# Escorna_CPU_2_40Amt.net
KiCad netlist of a schematic drawn in EAGLE
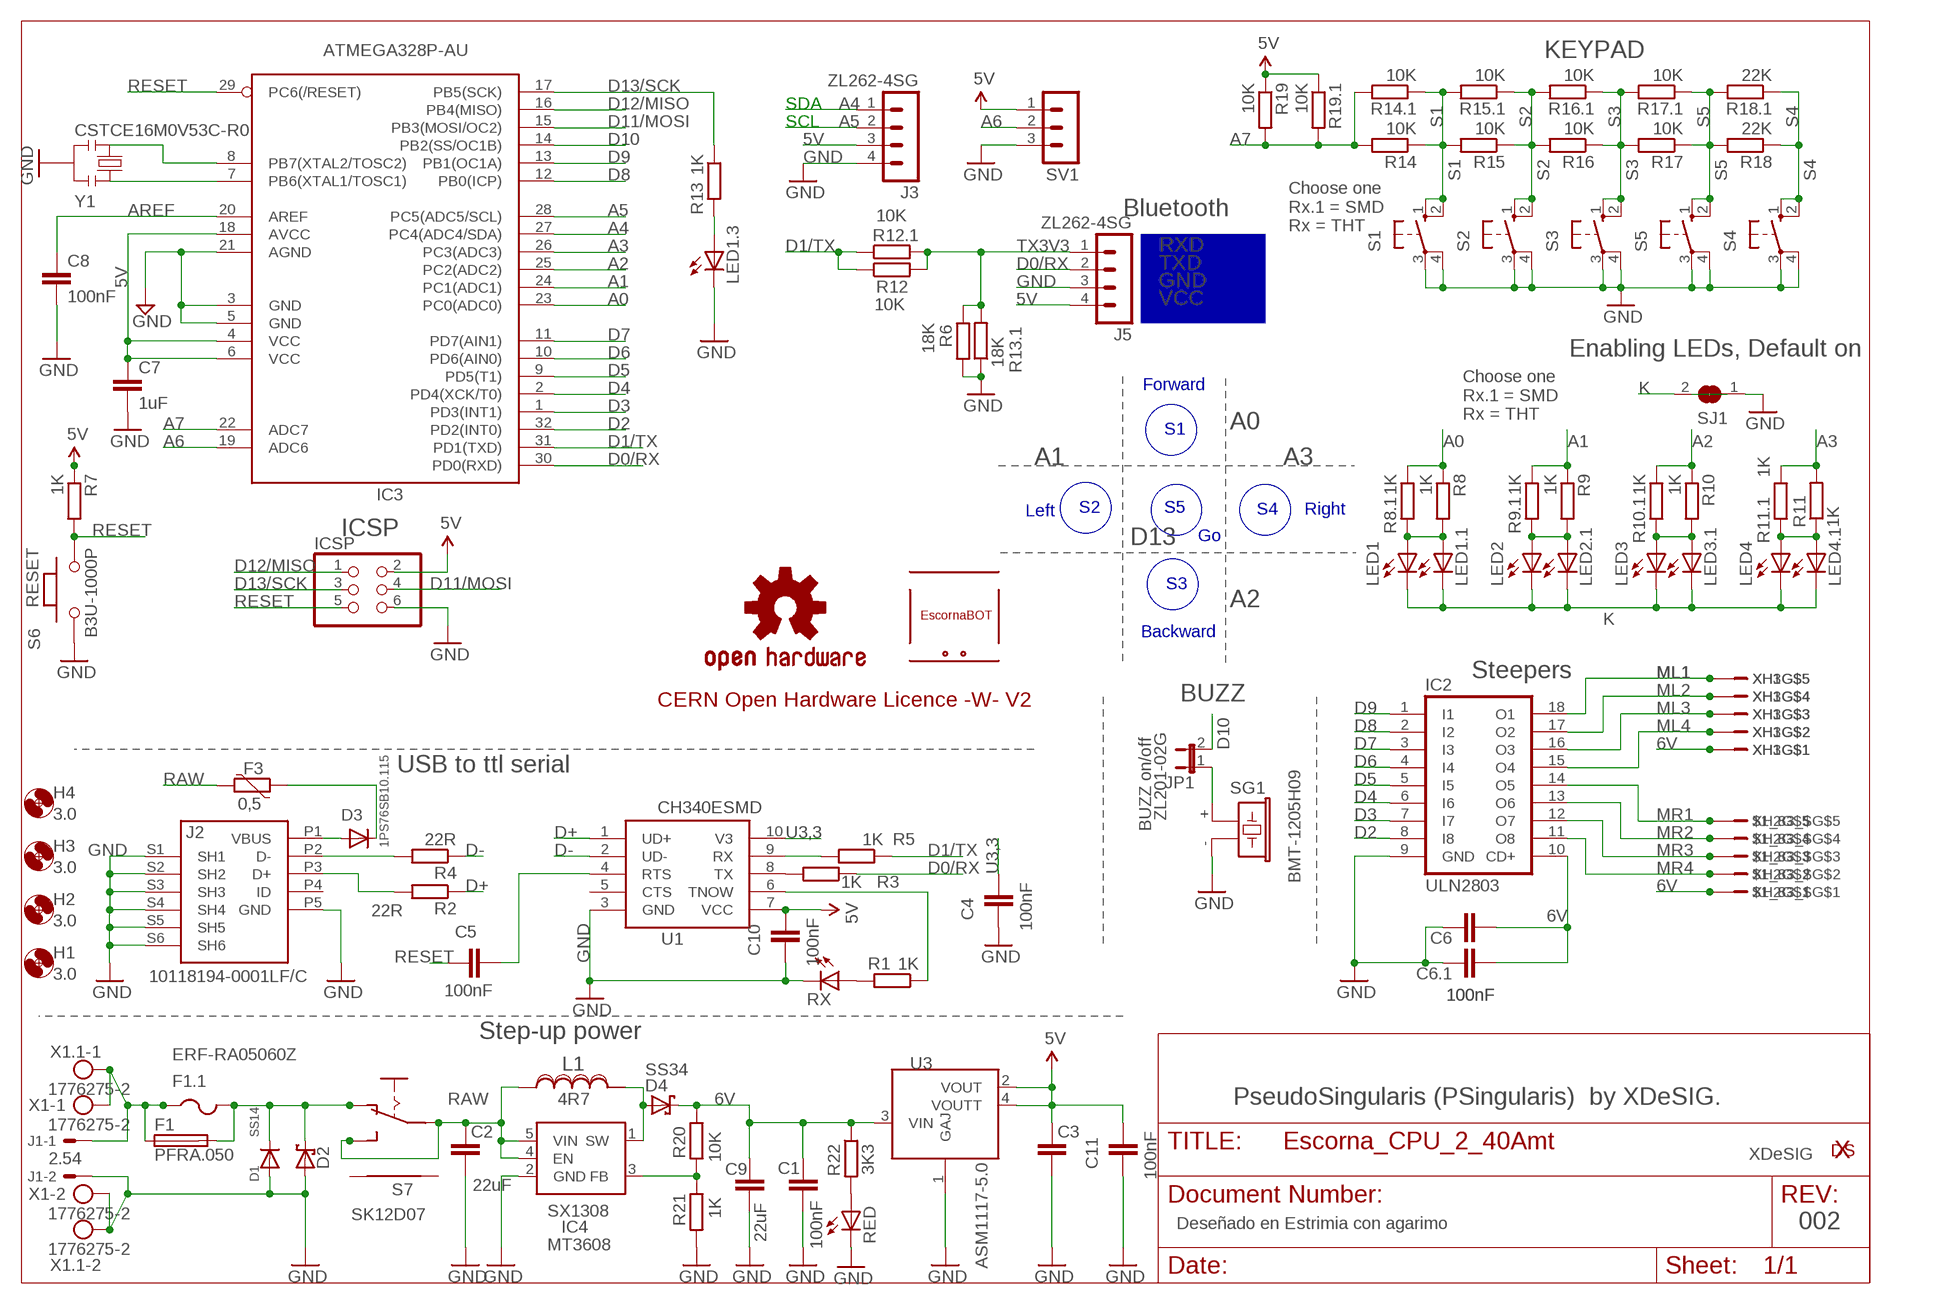
[diagram p0: schematic, sheet 1]

(export (version "E")
  (design (tool "Eeschema 10.0.6"))
  (components
    (comp (ref "$1_82_$")
      (value "XDESIG_XDESIG21")
      (footprint "eagle-import:XDESIG_XDESIG")
      (libsource (lib "eagle-import") (part "XDESIG_XDESIG21"))
    )
    (comp (ref "$1_83_$")
      (value "B5B-XH-A")
      (footprint "eagle-import:B5B-XH-A")
      (libsource (lib "eagle-import") (part "B5B-XH-A"))
    )
    (comp (ref "C1")
      (value "100nF")
      (footprint "eagle-import:C0603-ROUND")
      (fields (field (name "PART_NUMBER") "cl10b104kbnc"))
      (libsource (lib "eagle-import") (part "0015_100NF_0603"))
    )
    (comp (ref "C2")
      (value "22uF")
      (footprint "eagle-import:C1206K")
      (libsource (lib "eagle-import") (part "C-EUC1206K"))
    )
    (comp (ref "C3")
      (value "10uF")
      (footprint "eagle-import:C1206K")
      (libsource (lib "eagle-import") (part "C-EUC1206K"))
    )
    (comp (ref "C4")
      (value "100nF")
      (footprint "eagle-import:C0603-ROUND")
      (fields (field (name "PART_NUMBER") "cl10b104kbnc"))
      (libsource (lib "eagle-import") (part "0015_100NF_0603"))
    )
    (comp (ref "C5")
      (value "100nF")
      (footprint "eagle-import:C0603-ROUND")
      (fields (field (name "PART_NUMBER") "cl10b104kbnc"))
      (libsource (lib "eagle-import") (part "0015_100NF_0603"))
    )
    (comp (ref "C6")
      (value "100nF")
      (footprint "eagle-import:C025-024X044")
      (libsource (lib "eagle-import") (part "C-EU025-024X044"))
    )
    (comp (ref "C6.1")
      (value "100nF")
      (footprint "eagle-import:C0603K")
      (libsource (lib "eagle-import") (part "C-EUC0603K"))
    )
    (comp (ref "C7")
      (value "1uF")
      (footprint "eagle-import:C0603-ROUND")
      (fields (field (name "PART_NUMBER") "1uF_0603/GRM188R61E105KA12D"))
      (libsource (lib "eagle-import") (part "0006_1UF_0603/GRM188R61E105KA12D"))
    )
    (comp (ref "C8")
      (value "100nF")
      (footprint "eagle-import:C0603-ROUND")
      (fields (field (name "PART_NUMBER") "cl10b104kbnc"))
      (libsource (lib "eagle-import") (part "0015_100NF_0603"))
    )
    (comp (ref "C9")
      (value "22uF")
      (footprint "eagle-import:C1206K")
      (libsource (lib "eagle-import") (part "C-EUC1206K"))
    )
    (comp (ref "C10")
      (value "100nF")
      (footprint "eagle-import:C0603-ROUND")
      (fields (field (name "PART_NUMBER") "cl10b104kbnc"))
      (libsource (lib "eagle-import") (part "0015_100NF_0603"))
    )
    (comp (ref "C11")
      (value "100nF")
      (footprint "eagle-import:C0603-ROUND")
      (fields (field (name "PART_NUMBER") "cl10b104kbnc"))
      (libsource (lib "eagle-import") (part "0015_100NF_0603"))
    )
    (comp (ref "D1")
      (value "SS14")
      (footprint "eagle-import:SMADIODE")
      (libsource (lib "eagle-import") (part "DIODESMA"))
    )
    (comp (ref "D2")
      (value "1N5817")
      (footprint "eagle-import:DO41-10")
      (libsource (lib "eagle-import") (part "P4KEXX"))
    )
    (comp (ref "D3")
      (value "1PS76SB10.115")
      (footprint "eagle-import:SOD-323F")
      (libsource (lib "eagle-import") (part "DIODESOD-323F"))
    )
    (comp (ref "D4")
      (value "SS34")
      (footprint "eagle-import:DIODE_SMA")
      (libsource (lib "eagle-import") (part "DIODE_SCHOTTKY-DIODESMA"))
    )
    (comp (ref "ESC")
      (value "ESCORNABOT")
      (footprint "eagle-import:ESCORNA_PEQUE")
      (libsource (lib "eagle-import") (part "ESCORNABOT"))
    )
    (comp (ref "F1")
      (value "PFRA.050")
      (footprint "eagle-import:TE5")
      (libsource (lib "eagle-import") (part "FUSETE5"))
    )
    (comp (ref "F1.1")
      (value "ERF-RA05060Z")
      (footprint "eagle-import:R1206")
      (libsource (lib "eagle-import") (part "PTCFUSE-1206"))
    )
    (comp (ref "F3")
      (value "0,5")
      (footprint "eagle-import:R1206")
      (libsource (lib "eagle-import") (part "PTC1206L"))
    )
    (comp (ref "H1")
      (value "3.0")
      (footprint "eagle-import:3,0")
      (libsource (lib "eagle-import") (part "MOUNT-HOLE3.0"))
    )
    (comp (ref "H2")
      (value "3.0")
      (footprint "eagle-import:3,0")
      (libsource (lib "eagle-import") (part "MOUNT-HOLE3.0"))
    )
    (comp (ref "H3")
      (value "3.0")
      (footprint "eagle-import:3,0")
      (libsource (lib "eagle-import") (part "MOUNT-HOLE3.0"))
    )
    (comp (ref "H4")
      (value "3.0")
      (footprint "eagle-import:3,0")
      (libsource (lib "eagle-import") (part "MOUNT-HOLE3.0"))
    )
    (comp (ref "IC2")
      (value "ULN2803")
      (footprint "eagle-import:DIL18")
      (libsource (lib "eagle-import") (part "ULN2803A"))
    )
    (comp (ref "IC3")
      (value "ATMEGA328P-AU")
      (footprint "eagle-import:TQFP32-08")
      (libsource (lib "eagle-import") (part "0265_ATMEGA328P-AU"))
    )
    (comp (ref "IC4")
      (value "SX1308")
      (footprint "eagle-import:SOT23-6")
      (libsource (lib "eagle-import") (part "SX1308"))
    )
    (comp (ref "ICSP")
      (value "0114_PH254-203DF118A00V")
      (footprint "eagle-import:2X03")
      (fields (field (name "PART_NUMBER") "PH254-203DF118A00V"))
      (libsource (lib "eagle-import") (part "0114_PH254-203DF118A00V"))
    )
    (comp (ref "J1")
      (value "2.54")
      (footprint "eagle-import:6410-02")
      (libsource (lib "eagle-import") (part "22-?-0227-2021"))
    )
    (comp (ref "J2")
      (value "10118194-0001LF/C")
      (footprint "eagle-import:SMARTPRJ_CON2_USB_MICRO_B_AT")
      (libsource (lib "eagle-import") (part "SMARTPRJ_MYCON2_USB-MINI-B"))
    )
    (comp (ref "J3")
      (value "ZL262-4SG")
      (footprint "eagle-import:MA04-1")
      (libsource (lib "eagle-import") (part "MA04-1"))
    )
    (comp (ref "J5")
      (value "ZL262-4SG")
      (footprint "eagle-import:MA04-1")
      (libsource (lib "eagle-import") (part "MA04-1"))
    )
    (comp (ref "JP1")
      (value "ZL201-02G")
      (footprint "eagle-import:JP1")
      (libsource (lib "eagle-import") (part "JP1E"))
    )
    (comp (ref "L1")
      (value "4R7")
      (footprint "eagle-import:SRN6045")
      (fields (field (name "MF") "Bourns") (field (name "MP") "SRN6045-330M"))
      (libsource (lib "eagle-import") (part "SRN6045-330M6045"))
    )
    (comp (ref "LED1")
      (value "LED3MM")
      (footprint "eagle-import:LED3MM")
      (libsource (lib "eagle-import") (part "LED3MM"))
    )
    (comp (ref "LED1.1")
      (value "LEDCHIPLED_0603")
      (footprint "eagle-import:CHIPLED_0603")
      (libsource (lib "eagle-import") (part "LEDCHIPLED_0603"))
    )
    (comp (ref "LED1.3")
      (value "LEDCHIPLED_0603")
      (footprint "eagle-import:CHIPLED_0603")
      (libsource (lib "eagle-import") (part "LEDCHIPLED_0603"))
    )
    (comp (ref "LED2")
      (value "LED3MM")
      (footprint "eagle-import:LED3MM")
      (libsource (lib "eagle-import") (part "LED3MM"))
    )
    (comp (ref "LED2.1")
      (value "LEDCHIPLED_0603")
      (footprint "eagle-import:CHIPLED_0603")
      (libsource (lib "eagle-import") (part "LEDCHIPLED_0603"))
    )
    (comp (ref "LED3")
      (value "LED3MM")
      (footprint "eagle-import:LED3MM")
      (libsource (lib "eagle-import") (part "LED3MM"))
    )
    (comp (ref "LED3.1")
      (value "LEDCHIPLED_0603")
      (footprint "eagle-import:CHIPLED_0603")
      (libsource (lib "eagle-import") (part "LEDCHIPLED_0603"))
    )
    (comp (ref "LED4")
      (value "LED3MM")
      (footprint "eagle-import:LED3MM")
      (libsource (lib "eagle-import") (part "LED3MM"))
    )
    (comp (ref "LED4.1")
      (value "LEDCHIPLED_0603")
      (footprint "eagle-import:CHIPLED_0603")
      (libsource (lib "eagle-import") (part "LEDCHIPLED_0603"))
    )
    (comp (ref "LOGO2")
      (value "OSHW-LOGOL")
      (footprint "eagle-import:ESCORNA_LBRESCORNA_CPU_2_10_SPARKFUN-AESTHETICS_OSHW-LOGO-L")
      (libsource (lib "eagle-import") (part "OSHW-LOGOL"))
    )
    (comp (ref "R1")
      (value "1K")
      (footprint "eagle-import:R0603")
      (libsource (lib "eagle-import") (part "R-EU_R0603"))
    )
    (comp (ref "R2")
      (value "22R")
      (footprint "eagle-import:R0603")
      (libsource (lib "eagle-import") (part "R-EU_R0603"))
    )
    (comp (ref "R3")
      (value "1K")
      (footprint "eagle-import:R0603")
      (libsource (lib "eagle-import") (part "R-EU_R0603"))
    )
    (comp (ref "R4")
      (value "22R")
      (footprint "eagle-import:R0603")
      (libsource (lib "eagle-import") (part "R-EU_R0603"))
    )
    (comp (ref "R5")
      (value "1K")
      (footprint "eagle-import:R0603")
      (libsource (lib "eagle-import") (part "R-EU_R0603"))
    )
    (comp (ref "R6")
      (value "18K")
      (footprint "eagle-import:0204_7")
      (libsource (lib "eagle-import") (part "R-EU_0204/7"))
    )
    (comp (ref "R7")
      (value "1K")
      (footprint "eagle-import:R0603")
      (libsource (lib "eagle-import") (part "R-EU_R0603"))
    )
    (comp (ref "R8")
      (value "1K")
      (footprint "eagle-import:0204_7")
      (libsource (lib "eagle-import") (part "R-EU_0204/7"))
    )
    (comp (ref "R8.1")
      (value "1K")
      (footprint "eagle-import:R0603")
      (libsource (lib "eagle-import") (part "R-EU_R0603"))
    )
    (comp (ref "R9")
      (value "1K")
      (footprint "eagle-import:0204_7")
      (libsource (lib "eagle-import") (part "R-EU_0204/7"))
    )
    (comp (ref "R9.1")
      (value "1K")
      (footprint "eagle-import:R0603")
      (libsource (lib "eagle-import") (part "R-EU_R0603"))
    )
    (comp (ref "R10")
      (value "1K")
      (footprint "eagle-import:0204_7")
      (libsource (lib "eagle-import") (part "R-EU_0204/7"))
    )
    (comp (ref "R10.1")
      (value "1K")
      (footprint "eagle-import:R0603")
      (libsource (lib "eagle-import") (part "R-EU_R0603"))
    )
    (comp (ref "R11")
      (value "1K")
      (footprint "eagle-import:0204_7")
      (libsource (lib "eagle-import") (part "R-EU_0204/7"))
    )
    (comp (ref "R11.1")
      (value "1K")
      (footprint "eagle-import:R0603")
      (libsource (lib "eagle-import") (part "R-EU_R0603"))
    )
    (comp (ref "R12")
      (value "10K")
      (footprint "eagle-import:0204_7")
      (libsource (lib "eagle-import") (part "R-EU_0204/7"))
    )
    (comp (ref "R12.1")
      (value "10K")
      (footprint "eagle-import:R0603")
      (libsource (lib "eagle-import") (part "R-EU_R0603"))
    )
    (comp (ref "R13")
      (value "1K")
      (footprint "eagle-import:R0603")
      (libsource (lib "eagle-import") (part "R-EU_R0603"))
    )
    (comp (ref "R13.1")
      (value "18K")
      (footprint "eagle-import:R0603")
      (libsource (lib "eagle-import") (part "R-EU_R0603"))
    )
    (comp (ref "R14")
      (value "10K")
      (footprint "eagle-import:0204_7")
      (libsource (lib "eagle-import") (part "R-EU_0204/7"))
    )
    (comp (ref "R14.1")
      (value "10K")
      (footprint "eagle-import:R0603")
      (libsource (lib "eagle-import") (part "R-EU_R0603"))
    )
    (comp (ref "R15")
      (value "10K")
      (footprint "eagle-import:0204_7")
      (libsource (lib "eagle-import") (part "R-EU_0204/7"))
    )
    (comp (ref "R15.1")
      (value "10K")
      (footprint "eagle-import:R0603")
      (libsource (lib "eagle-import") (part "R-EU_R0603"))
    )
    (comp (ref "R16")
      (value "10K")
      (footprint "eagle-import:0204_7")
      (libsource (lib "eagle-import") (part "R-EU_0204/7"))
    )
    (comp (ref "R16.1")
      (value "10K")
      (footprint "eagle-import:R0603")
      (libsource (lib "eagle-import") (part "R-EU_R0603"))
    )
    (comp (ref "R17")
      (value "10K")
      (footprint "eagle-import:0204_7")
      (libsource (lib "eagle-import") (part "R-EU_0204/7"))
    )
    (comp (ref "R17.1")
      (value "10K")
      (footprint "eagle-import:R0603")
      (libsource (lib "eagle-import") (part "R-EU_R0603"))
    )
    (comp (ref "R18")
      (value "22K")
      (footprint "eagle-import:0204_7")
      (libsource (lib "eagle-import") (part "R-EU_0204/7"))
    )
    (comp (ref "R18.1")
      (value "22K")
      (footprint "eagle-import:R0603")
      (libsource (lib "eagle-import") (part "R-EU_R0603"))
    )
    (comp (ref "R19")
      (value "10K")
      (footprint "eagle-import:0204_7")
      (libsource (lib "eagle-import") (part "R-EU_0204/7"))
    )
    (comp (ref "R19.1")
      (value "10K")
      (footprint "eagle-import:R0603")
      (libsource (lib "eagle-import") (part "R-EU_R0603"))
    )
    (comp (ref "R20")
      (value "10K")
      (footprint "eagle-import:R0603")
      (libsource (lib "eagle-import") (part "R-EU_R0603"))
    )
    (comp (ref "R21")
      (value "1K")
      (footprint "eagle-import:R0603")
      (libsource (lib "eagle-import") (part "R-EU_R0603"))
    )
    (comp (ref "R22")
      (value "3K3")
      (footprint "eagle-import:R0603")
      (libsource (lib "eagle-import") (part "R-EU_R0603"))
    )
    (comp (ref "RED")
      (value "LEDCHIPLED_0603")
      (footprint "eagle-import:CHIPLED_0603")
      (libsource (lib "eagle-import") (part "LEDCHIPLED_0603"))
    )
    (comp (ref "RX")
      (value "LEDCHIPLED_0603")
      (footprint "eagle-import:CHIPLED_0603")
      (libsource (lib "eagle-import") (part "LEDCHIPLED_0603"))
    )
    (comp (ref "S1")
      (value "40-XX")
      (footprint "eagle-import:B3F-40")
      (fields (field (name "MF") "OMRON COMPONENTS USA") (field (name "MPN") "B3F-4000"))
      (libsource (lib "eagle-import") (part "40-XX"))
    )
    (comp (ref "S2")
      (value "40-XX")
      (footprint "eagle-import:B3F-40")
      (fields (field (name "MF") "OMRON COMPONENTS USA") (field (name "MPN") "B3F-4000"))
      (libsource (lib "eagle-import") (part "40-XX"))
    )
    (comp (ref "S3")
      (value "40-XX")
      (footprint "eagle-import:B3F-40")
      (fields (field (name "MF") "OMRON COMPONENTS USA") (field (name "MPN") "B3F-4000"))
      (libsource (lib "eagle-import") (part "40-XX"))
    )
    (comp (ref "S4")
      (value "40-XX")
      (footprint "eagle-import:B3F-40")
      (fields (field (name "MF") "OMRON COMPONENTS USA") (field (name "MPN") "B3F-4000"))
      (libsource (lib "eagle-import") (part "40-XX"))
    )
    (comp (ref "S5")
      (value "40-XX")
      (footprint "eagle-import:B3F-40")
      (fields (field (name "MF") "OMRON COMPONENTS USA") (field (name "MPN") "B3F-4000"))
      (libsource (lib "eagle-import") (part "40-XX"))
    )
    (comp (ref "S6")
      (value "B3U-1000P")
      (footprint "eagle-import:SMD_157SW")
      (fields (field (name "PART_NUMBER") "IT-1185AP1C-160G-G_T&R"))
      (libsource (lib "eagle-import") (part "0173_IT-1185AP1C-160G-G_T&R"))
    )
    (comp (ref "S7")
      (value "SK12D07")
      (footprint "eagle-import:ESCORNA_SK-12D07")
      (libsource (lib "eagle-import") (part "ESCORNA_SK12F14D"))
    )
    (comp (ref "SG1")
      (value "BMT-1205H09")
      (footprint "eagle-import:F_CM12P")
      (libsource (lib "eagle-import") (part "F/CM12P"))
    )
    (comp (ref "SJ1") (value "SJ") (footprint "eagle-import:SJ") (libsource (lib "eagle-import") (part "SJ")))
    (comp (ref "SV1")
      (value "MA03-1")
      (footprint "eagle-import:MA03-1")
      (libsource (lib "eagle-import") (part "MA03-1"))
    )
    (comp (ref "U1")
      (value "CH340ESMD")
      (footprint "eagle-import:MSOP10")
      (fields (field (name "MF") "WCH") (field (name "MP") "CH340E"))
      (libsource (lib "eagle-import") (part "CH340ESMD"))
    )
    (comp (ref "U3")
      (value "ASM1117-5.0")
      (footprint "eagle-import:SOT223")
      (libsource (lib "eagle-import") (part "ASM1117-3.3"))
    )
    (comp (ref "X1")
      (value "1776275-2")
      (footprint "eagle-import:AK550_2")
      (libsource (lib "eagle-import") (part "AK550/2"))
    )
    (comp (ref "X1.1")
      (value "1776275-2")
      (footprint "eagle-import:AK550_2")
      (fields (field (name "OC_FARNELL") "unknown") (field (name "OC_NEWARK") "unknown"))
      (libsource (lib "eagle-import") (part "AK550/2"))
    )
    (comp (ref "XH1")
      (value "B5B-XH-A")
      (footprint "eagle-import:B5B-XH-A")
      (libsource (lib "eagle-import") (part "B5B-XH-A"))
    )
    (comp (ref "XH2")
      (value "B5B-XH-A")
      (footprint "eagle-import:B5B-XH-A")
      (libsource (lib "eagle-import") (part "B5B-XH-A"))
    )
    (comp (ref "XH3")
      (value "B5B-XH-A")
      (footprint "eagle-import:B5B-XH-A")
      (libsource (lib "eagle-import") (part "B5B-XH-A"))
    )
    (comp (ref "Y1")
      (value "CSTCE16M0V53C-R0")
      (footprint "eagle-import:RESONATOR")
      (fields (field (name "PART_NUMBER") "CSTCE16M0V53-R0"))
      (libsource (lib "eagle-import") (part "0011_CSTCE16M0V53-R0"))
    )
  )
  (nets
    (net (code "1") (name "/6V") (class "Default")
      (node (ref "$1_83_$") (pin "P$1") (pinfunction "1_P$1") (pintype "passive"))
      (node (ref "C1") (pin "2") (pinfunction "2_2") (pintype "passive"))
      (node (ref "C6") (pin "2") (pinfunction "2_2") (pintype "passive"))
      (node (ref "C6.1") (pin "2") (pinfunction "2_2") (pintype "passive"))
      (node (ref "C9") (pin "2") (pinfunction "2_2") (pintype "passive"))
      (node (ref "D4") (pin "C") (pinfunction "C_C") (pintype "passive"))
      (node (ref "IC2") (pin "10") (pinfunction "CD+_10") (pintype "passive"))
      (node (ref "R20") (pin "1") (pinfunction "1_1") (pintype "passive"))
      (node (ref "R22") (pin "1") (pinfunction "1_1") (pintype "passive"))
      (node (ref "U3") (pin "3") (pinfunction "VIN_3") (pintype "bidirectional"))
      (node (ref "XH1") (pin "P$1") (pinfunction "1_P$1") (pintype "passive"))
      (node (ref "XH2") (pin "P$1") (pinfunction "1_P$1") (pintype "passive"))
      (node (ref "XH3") (pin "P$1") (pinfunction "1_P$1") (pintype "passive"))
    )
    (net (code "2") (name "/A0") (class "Default")
      (node (ref "IC3") (pin "23") (pinfunction "PC0(ADC0)_23") (pintype "bidirectional"))
      (node (ref "R8") (pin "1") (pinfunction "1_1") (pintype "passive"))
      (node (ref "R8.1") (pin "1") (pinfunction "1_1") (pintype "passive"))
    )
    (net (code "3") (name "/A1") (class "Default")
      (node (ref "IC3") (pin "24") (pinfunction "PC1(ADC1)_24") (pintype "bidirectional"))
      (node (ref "R9") (pin "1") (pinfunction "1_1") (pintype "passive"))
      (node (ref "R9.1") (pin "1") (pinfunction "1_1") (pintype "passive"))
    )
    (net (code "4") (name "/A2") (class "Default")
      (node (ref "IC3") (pin "25") (pinfunction "PC2(ADC2)_25") (pintype "bidirectional"))
      (node (ref "R10") (pin "1") (pinfunction "1_1") (pintype "passive"))
      (node (ref "R10.1") (pin "1") (pinfunction "1_1") (pintype "passive"))
    )
    (net (code "5") (name "/A3") (class "Default")
      (node (ref "IC3") (pin "26") (pinfunction "PC3(ADC3)_26") (pintype "bidirectional"))
      (node (ref "R11") (pin "2") (pinfunction "2_2") (pintype "passive"))
      (node (ref "R11.1") (pin "1") (pinfunction "1_1") (pintype "passive"))
    )
    (net (code "6") (name "/A4") (class "Default")
      (node (ref "IC3") (pin "27") (pinfunction "PC4(ADC4/SDA)_27") (pintype "bidirectional"))
      (node (ref "J3") (pin "1") (pinfunction "1_1") (pintype "passive"))
    )
    (net (code "7") (name "/A5") (class "Default")
      (node (ref "IC3") (pin "28") (pinfunction "PC5(ADC5/SCL)_28") (pintype "bidirectional"))
      (node (ref "J3") (pin "2") (pinfunction "2_2") (pintype "passive"))
    )
    (net (code "8") (name "/A6") (class "Default")
      (node (ref "IC3") (pin "19") (pinfunction "ADC6_19") (pintype "bidirectional"))
      (node (ref "SV1") (pin "2") (pinfunction "2_2") (pintype "passive"))
    )
    (net (code "9") (name "/A7") (class "Default")
      (node (ref "IC3") (pin "22") (pinfunction "ADC7_22") (pintype "bidirectional"))
      (node (ref "R14") (pin "2") (pinfunction "2_2") (pintype "passive"))
      (node (ref "R14.1") (pin "2") (pinfunction "2_2") (pintype "passive"))
      (node (ref "R19") (pin "2") (pinfunction "2_2") (pintype "passive"))
      (node (ref "R19.1") (pin "2") (pinfunction "2_2") (pintype "passive"))
    )
    (net (code "10") (name "/AREF") (class "Default")
      (node (ref "C8") (pin "1") (pinfunction "1_1") (pintype "passive"))
      (node (ref "IC3") (pin "20") (pinfunction "AREF_20") (pintype "bidirectional"))
    )
    (net (code "11") (name "/D+") (class "Default")
      (node (ref "R2") (pin "1") (pinfunction "1_1") (pintype "passive"))
      (node (ref "U1") (pin "1") (pinfunction "UD+_1") (pintype "bidirectional"))
    )
    (net (code "12") (name "/D-") (class "Default")
      (node (ref "R4") (pin "1") (pinfunction "1_1") (pintype "passive"))
      (node (ref "U1") (pin "2") (pinfunction "UD-_2") (pintype "bidirectional"))
    )
    (net (code "13") (name "/D0{slash}RX") (class "Default")
      (node (ref "IC3") (pin "30") (pinfunction "PD0(RXD)_30") (pintype "bidirectional"))
      (node (ref "J5") (pin "2") (pinfunction "2_2") (pintype "passive"))
      (node (ref "R3") (pin "1") (pinfunction "1_1") (pintype "passive"))
    )
    (net (code "14") (name "/D1{slash}TX") (class "Default")
      (node (ref "IC3") (pin "31") (pinfunction "PD1(TXD)_31") (pintype "bidirectional"))
      (node (ref "R12") (pin "1") (pinfunction "1_1") (pintype "passive"))
      (node (ref "R12.1") (pin "1") (pinfunction "1_1") (pintype "passive"))
      (node (ref "R5") (pin "1") (pinfunction "1_1") (pintype "passive"))
    )
    (net (code "15") (name "/D2") (class "Default")
      (node (ref "IC2") (pin "8") (pinfunction "I8_8") (pintype "input"))
      (node (ref "IC3") (pin "32") (pinfunction "PD2(INT0)_32") (pintype "bidirectional"))
    )
    (net (code "16") (name "/D3") (class "Default")
      (node (ref "IC2") (pin "7") (pinfunction "I7_7") (pintype "input"))
      (node (ref "IC3") (pin "1") (pinfunction "PD3(INT1)_1") (pintype "bidirectional"))
    )
    (net (code "17") (name "/D4") (class "Default")
      (node (ref "IC2") (pin "6") (pinfunction "I6_6") (pintype "input"))
      (node (ref "IC3") (pin "2") (pinfunction "PD4(XCK/T0)_2") (pintype "bidirectional"))
    )
    (net (code "18") (name "/D5") (class "Default")
      (node (ref "IC2") (pin "5") (pinfunction "I5_5") (pintype "input"))
      (node (ref "IC3") (pin "9") (pinfunction "PD5(T1)_9") (pintype "bidirectional"))
    )
    (net (code "19") (name "/D6") (class "Default")
      (node (ref "IC2") (pin "4") (pinfunction "I4_4") (pintype "input"))
      (node (ref "IC3") (pin "10") (pinfunction "PD6(AIN0)_10") (pintype "bidirectional"))
    )
    (net (code "20") (name "/D7") (class "Default")
      (node (ref "IC2") (pin "3") (pinfunction "I3_3") (pintype "input"))
      (node (ref "IC3") (pin "11") (pinfunction "PD7(AIN1)_11") (pintype "bidirectional"))
    )
    (net (code "21") (name "/D8") (class "Default")
      (node (ref "IC2") (pin "2") (pinfunction "I2_2") (pintype "input"))
      (node (ref "IC3") (pin "12") (pinfunction "PB0(ICP)_12") (pintype "bidirectional"))
    )
    (net (code "22") (name "/D9") (class "Default")
      (node (ref "IC2") (pin "1") (pinfunction "I1_1") (pintype "input"))
      (node (ref "IC3") (pin "13") (pinfunction "PB1(OC1A)_13") (pintype "bidirectional"))
    )
    (net (code "23") (name "/D10") (class "Default")
      (node (ref "IC3") (pin "14") (pinfunction "PB2(SS/OC1B)_14") (pintype "bidirectional"))
      (node (ref "JP1") (pin "2") (pinfunction "2_2") (pintype "passive"))
    )
    (net (code "24") (name "/D11{slash}MOSI") (class "Default")
      (node (ref "IC3") (pin "15") (pinfunction "PB3(MOSI/OC2)_15") (pintype "bidirectional"))
      (node (ref "ICSP") (pin "4") (pinfunction "4_4") (pintype "passive"))
    )
    (net (code "25") (name "/D12{slash}MISO") (class "Default")
      (node (ref "IC3") (pin "16") (pinfunction "PB4(MISO)_16") (pintype "bidirectional"))
      (node (ref "ICSP") (pin "1") (pinfunction "1_1") (pintype "passive"))
    )
    (net (code "26") (name "/D13{slash}SCK") (class "Default")
      (node (ref "IC3") (pin "17") (pinfunction "PB5(SCK)_17") (pintype "bidirectional"))
      (node (ref "ICSP") (pin "3") (pinfunction "3_3") (pintype "passive"))
      (node (ref "R13") (pin "1") (pinfunction "1_1") (pintype "passive"))
    )
    (net (code "27") (name "/K") (class "Default")
      (node (ref "LED1") (pin "K") (pinfunction "C_K") (pintype "passive"))
      (node (ref "LED1.1") (pin "C") (pinfunction "C_C") (pintype "passive"))
      (node (ref "LED2") (pin "K") (pinfunction "C_K") (pintype "passive"))
      (node (ref "LED2.1") (pin "C") (pinfunction "C_C") (pintype "passive"))
      (node (ref "LED3") (pin "K") (pinfunction "C_K") (pintype "passive"))
      (node (ref "LED3.1") (pin "C") (pinfunction "C_C") (pintype "passive"))
      (node (ref "LED4") (pin "K") (pinfunction "C_K") (pintype "passive"))
      (node (ref "LED4.1") (pin "C") (pinfunction "C_C") (pintype "passive"))
      (node (ref "SJ1") (pin "2") (pinfunction "2_2") (pintype "passive"))
    )
    (net (code "28") (name "/ML1") (class "Default")
      (node (ref "IC2") (pin "18") (pinfunction "O1_18") (pintype "open_collector"))
      (node (ref "XH1") (pin "P$5") (pinfunction "1_P$5") (pintype "passive"))
      (node (ref "XH3") (pin "P$5") (pinfunction "1_P$5") (pintype "passive"))
    )
    (net (code "29") (name "/ML2") (class "Default")
      (node (ref "IC2") (pin "17") (pinfunction "O2_17") (pintype "open_collector"))
      (node (ref "XH1") (pin "P$4") (pinfunction "1_P$4") (pintype "passive"))
      (node (ref "XH3") (pin "P$4") (pinfunction "1_P$4") (pintype "passive"))
    )
    (net (code "30") (name "/ML3") (class "Default")
      (node (ref "IC2") (pin "16") (pinfunction "O3_16") (pintype "open_collector"))
      (node (ref "XH1") (pin "P$3") (pinfunction "1_P$3") (pintype "passive"))
      (node (ref "XH3") (pin "P$3") (pinfunction "1_P$3") (pintype "passive"))
    )
    (net (code "31") (name "/ML4") (class "Default")
      (node (ref "IC2") (pin "15") (pinfunction "O4_15") (pintype "open_collector"))
      (node (ref "XH1") (pin "P$2") (pinfunction "1_P$2") (pintype "passive"))
      (node (ref "XH3") (pin "P$2") (pinfunction "1_P$2") (pintype "passive"))
    )
    (net (code "32") (name "/MR1") (class "Default")
      (node (ref "$1_83_$") (pin "P$5") (pinfunction "1_P$5") (pintype "passive"))
      (node (ref "IC2") (pin "14") (pinfunction "O5_14") (pintype "open_collector"))
      (node (ref "XH2") (pin "P$5") (pinfunction "1_P$5") (pintype "passive"))
    )
    (net (code "33") (name "/MR2") (class "Default")
      (node (ref "$1_83_$") (pin "P$4") (pinfunction "1_P$4") (pintype "passive"))
      (node (ref "IC2") (pin "13") (pinfunction "O6_13") (pintype "open_collector"))
      (node (ref "XH2") (pin "P$4") (pinfunction "1_P$4") (pintype "passive"))
    )
    (net (code "34") (name "/MR3") (class "Default")
      (node (ref "$1_83_$") (pin "P$3") (pinfunction "1_P$3") (pintype "passive"))
      (node (ref "IC2") (pin "12") (pinfunction "O7_12") (pintype "open_collector"))
      (node (ref "XH2") (pin "P$3") (pinfunction "1_P$3") (pintype "passive"))
    )
    (net (code "35") (name "/MR4") (class "Default")
      (node (ref "$1_83_$") (pin "P$2") (pinfunction "1_P$2") (pintype "passive"))
      (node (ref "IC2") (pin "11") (pinfunction "O8_11") (pintype "open_collector"))
      (node (ref "XH2") (pin "P$2") (pinfunction "1_P$2") (pintype "passive"))
    )
    (net (code "36") (name "/RAW") (class "Default")
      (node (ref "C2") (pin "2") (pinfunction "2_2") (pintype "passive"))
      (node (ref "F3") (pin "2") (pinfunction "2_2") (pintype "passive"))
      (node (ref "IC4") (pin "4") (pinfunction "EN_4") (pintype "bidirectional"))
      (node (ref "IC4") (pin "5") (pinfunction "VIN_5") (pintype "bidirectional"))
      (node (ref "L1") (pin "2") (pinfunction "2_2") (pintype "passive"))
      (node (ref "S7") (pin "P$1") (pinfunction "P_P$1") (pintype "passive"))
      (node (ref "S7") (pin "P$3") (pinfunction "S_P$3") (pintype "passive"))
    )
    (net (code "37") (name "/RESET") (class "Default")
      (node (ref "C5") (pin "1") (pinfunction "1_1") (pintype "passive"))
      (node (ref "IC3") (pin "29") (pinfunction "PC6(/RESET)_29") (pintype "bidirectional"))
      (node (ref "ICSP") (pin "5") (pinfunction "5_5") (pintype "passive"))
      (node (ref "R7") (pin "2") (pinfunction "2_2") (pintype "passive"))
      (node (ref "S6") (pin "2") (pinfunction "2_2") (pintype "passive"))
    )
    (net (code "38") (name "/S1") (class "Default")
      (node (ref "R14") (pin "1") (pinfunction "1_1") (pintype "passive"))
      (node (ref "R14.1") (pin "1") (pinfunction "1_1") (pintype "passive"))
      (node (ref "R15") (pin "2") (pinfunction "2_2") (pintype "passive"))
      (node (ref "R15.1") (pin "2") (pinfunction "2_2") (pintype "passive"))
      (node (ref "S1") (pin "1") (pinfunction "S_1") (pintype "passive"))
      (node (ref "S1") (pin "2") (pinfunction "S1_2") (pintype "passive"))
    )
    (net (code "39") (name "/S2") (class "Default")
      (node (ref "R15") (pin "1") (pinfunction "1_1") (pintype "passive"))
      (node (ref "R15.1") (pin "1") (pinfunction "1_1") (pintype "passive"))
      (node (ref "R16") (pin "2") (pinfunction "2_2") (pintype "passive"))
      (node (ref "R16.1") (pin "2") (pinfunction "2_2") (pintype "passive"))
      (node (ref "S2") (pin "1") (pinfunction "S_1") (pintype "passive"))
      (node (ref "S2") (pin "2") (pinfunction "S1_2") (pintype "passive"))
    )
    (net (code "40") (name "/S3") (class "Default")
      (node (ref "R16") (pin "1") (pinfunction "1_1") (pintype "passive"))
      (node (ref "R16.1") (pin "1") (pinfunction "1_1") (pintype "passive"))
      (node (ref "R17") (pin "2") (pinfunction "2_2") (pintype "passive"))
      (node (ref "R17.1") (pin "2") (pinfunction "2_2") (pintype "passive"))
      (node (ref "S3") (pin "1") (pinfunction "S_1") (pintype "passive"))
      (node (ref "S3") (pin "2") (pinfunction "S1_2") (pintype "passive"))
    )
    (net (code "41") (name "/S4") (class "Default")
      (node (ref "R18") (pin "1") (pinfunction "1_1") (pintype "passive"))
      (node (ref "R18.1") (pin "1") (pinfunction "1_1") (pintype "passive"))
      (node (ref "S4") (pin "1") (pinfunction "S_1") (pintype "passive"))
      (node (ref "S4") (pin "2") (pinfunction "S1_2") (pintype "passive"))
    )
    (net (code "42") (name "/S5") (class "Default")
      (node (ref "R17") (pin "1") (pinfunction "1_1") (pintype "passive"))
      (node (ref "R17.1") (pin "1") (pinfunction "1_1") (pintype "passive"))
      (node (ref "R18") (pin "2") (pinfunction "2_2") (pintype "passive"))
      (node (ref "R18.1") (pin "2") (pinfunction "2_2") (pintype "passive"))
      (node (ref "S5") (pin "1") (pinfunction "S_1") (pintype "passive"))
      (node (ref "S5") (pin "2") (pinfunction "S1_2") (pintype "passive"))
    )
    (net (code "43") (name "/TX3V3") (class "Default")
      (node (ref "J5") (pin "1") (pinfunction "1_1") (pintype "passive"))
      (node (ref "R12") (pin "2") (pinfunction "2_2") (pintype "passive"))
      (node (ref "R12.1") (pin "2") (pinfunction "2_2") (pintype "passive"))
      (node (ref "R13.1") (pin "2") (pinfunction "2_2") (pintype "passive"))
      (node (ref "R6") (pin "1") (pinfunction "1_1") (pintype "passive"))
    )
    (net (code "44") (name "/U3,3") (class "Default")
      (node (ref "C4") (pin "2") (pinfunction "2_2") (pintype "passive"))
      (node (ref "U1") (pin "10") (pinfunction "V3_10") (pintype "power_in"))
    )
    (net (code "45") (name "5V") (class "Default")
      (node (ref "C10") (pin "2") (pinfunction "2_2") (pintype "passive"))
      (node (ref "C11") (pin "2") (pinfunction "2_2") (pintype "passive"))
      (node (ref "C3") (pin "2") (pinfunction "2_2") (pintype "passive"))
      (node (ref "C7") (pin "1") (pinfunction "1_1") (pintype "passive"))
      (node (ref "IC3") (pin "18") (pinfunction "AVCC_18") (pintype "bidirectional"))
      (node (ref "IC3") (pin "4") (pinfunction "VCC_4") (pintype "bidirectional"))
      (node (ref "IC3") (pin "6") (pinfunction "VCC_6") (pintype "bidirectional"))
      (node (ref "ICSP") (pin "2") (pinfunction "2_2") (pintype "passive"))
      (node (ref "J3") (pin "3") (pinfunction "3_3") (pintype "passive"))
      (node (ref "J5") (pin "4") (pinfunction "4_4") (pintype "passive"))
      (node (ref "R19") (pin "1") (pinfunction "1_1") (pintype "passive"))
      (node (ref "R19.1") (pin "1") (pinfunction "1_1") (pintype "passive"))
      (node (ref "R7") (pin "1") (pinfunction "1_1") (pintype "passive"))
      (node (ref "SV1") (pin "1") (pinfunction "1_1") (pintype "passive"))
      (node (ref "U1") (pin "7") (pinfunction "VCC_7") (pintype "power_in"))
      (node (ref "U3") (pin "2") (pinfunction "VOUT_2") (pintype "bidirectional"))
      (node (ref "U3") (pin "4") (pinfunction "VOUTT_4") (pintype "bidirectional"))
    )
    (net (code "46") (name "GND") (class "Default")
      (node (ref "C1") (pin "1") (pinfunction "1_1") (pintype "passive"))
      (node (ref "C10") (pin "1") (pinfunction "1_1") (pintype "passive"))
      (node (ref "C11") (pin "1") (pinfunction "1_1") (pintype "passive"))
      (node (ref "C2") (pin "1") (pinfunction "1_1") (pintype "passive"))
      (node (ref "C3") (pin "1") (pinfunction "1_1") (pintype "passive"))
      (node (ref "C4") (pin "1") (pinfunction "1_1") (pintype "passive"))
      (node (ref "C6") (pin "1") (pinfunction "1_1") (pintype "passive"))
      (node (ref "C6.1") (pin "1") (pinfunction "1_1") (pintype "passive"))
      (node (ref "C7") (pin "2") (pinfunction "2_2") (pintype "passive"))
      (node (ref "C8") (pin "2") (pinfunction "2_2") (pintype "passive"))
      (node (ref "C9") (pin "1") (pinfunction "1_1") (pintype "passive"))
      (node (ref "D1") (pin "A") (pinfunction "A_A") (pintype "passive"))
      (node (ref "D2") (pin "A") (pinfunction "A_A") (pintype "passive"))
      (node (ref "IC2") (pin "9") (pinfunction "GND_9") (pintype "power_in"))
      (node (ref "IC3") (pin "21") (pinfunction "AGND_21") (pintype "bidirectional"))
      (node (ref "IC3") (pin "3") (pinfunction "GND_3") (pintype "bidirectional"))
      (node (ref "IC3") (pin "5") (pinfunction "GND_5") (pintype "bidirectional"))
      (node (ref "IC4") (pin "2") (pinfunction "GND_2") (pintype "bidirectional"))
      (node (ref "ICSP") (pin "6") (pinfunction "6_6") (pintype "passive"))
      (node (ref "J1") (pin "2") (pinfunction "S_2") (pintype "passive"))
      (node (ref "J2") (pin "P5") (pinfunction "GND_P5") (pintype "passive"))
      (node (ref "J2") (pin "S1") (pinfunction "SH1_S1") (pintype "passive"))
      (node (ref "J2") (pin "S2") (pinfunction "SH2_S2") (pintype "passive"))
      (node (ref "J2") (pin "S3") (pinfunction "SH3_S3") (pintype "passive"))
      (node (ref "J2") (pin "S4") (pinfunction "SH4_S4") (pintype "passive"))
      (node (ref "J2") (pin "S5") (pinfunction "SH5_S5") (pintype "passive"))
      (node (ref "J2") (pin "S6") (pinfunction "SH6_S6") (pintype "passive"))
      (node (ref "J3") (pin "4") (pinfunction "4_4") (pintype "passive"))
      (node (ref "J5") (pin "3") (pinfunction "3_3") (pintype "passive"))
      (node (ref "LED1.3") (pin "C") (pinfunction "C_C") (pintype "passive"))
      (node (ref "R13.1") (pin "1") (pinfunction "1_1") (pintype "passive"))
      (node (ref "R21") (pin "2") (pinfunction "2_2") (pintype "passive"))
      (node (ref "R6") (pin "2") (pinfunction "2_2") (pintype "passive"))
      (node (ref "RED") (pin "C") (pinfunction "C_C") (pintype "passive"))
      (node (ref "RX") (pin "C") (pinfunction "C_C") (pintype "passive"))
      (node (ref "S1") (pin "3") (pinfunction "P_3") (pintype "passive"))
      (node (ref "S1") (pin "4") (pinfunction "P1_4") (pintype "passive"))
      (node (ref "S2") (pin "3") (pinfunction "P_3") (pintype "passive"))
      (node (ref "S2") (pin "4") (pinfunction "P1_4") (pintype "passive"))
      (node (ref "S3") (pin "3") (pinfunction "P_3") (pintype "passive"))
      (node (ref "S3") (pin "4") (pinfunction "P1_4") (pintype "passive"))
      (node (ref "S4") (pin "3") (pinfunction "P_3") (pintype "passive"))
      (node (ref "S4") (pin "4") (pinfunction "P1_4") (pintype "passive"))
      (node (ref "S5") (pin "3") (pinfunction "P_3") (pintype "passive"))
      (node (ref "S5") (pin "4") (pinfunction "P1_4") (pintype "passive"))
      (node (ref "S6") (pin "1") (pinfunction "1_1") (pintype "passive"))
      (node (ref "SG1") (pin "-") (pinfunction "2_-") (pintype "passive"))
      (node (ref "SJ1") (pin "1") (pinfunction "1_1") (pintype "passive"))
      (node (ref "SV1") (pin "3") (pinfunction "3_3") (pintype "passive"))
      (node (ref "U1") (pin "3") (pinfunction "GND_3") (pintype "power_in"))
      (node (ref "U3") (pin "1") (pinfunction "GAJ_1") (pintype "bidirectional"))
      (node (ref "X1") (pin "2") (pinfunction "KL_2") (pintype "passive"))
      (node (ref "X1.1") (pin "2") (pinfunction "KL_2") (pintype "passive"))
      (node (ref "Y1") (pin "2") (pinfunction "2_2") (pintype "passive"))
    )
    (net (code "47") (name "Net-(D3-PadC)") (class "Default")
      (node (ref "D3") (pin "C") (pinfunction "C_C") (pintype "passive"))
      (node (ref "F3") (pin "1") (pinfunction "1_1") (pintype "passive"))
    )
    (net (code "48") (name "Net-(IC3-PB6(XTAL1{slash}TOSC1))") (class "Default")
      (node (ref "IC3") (pin "7") (pinfunction "PB6(XTAL1/TOSC1)_7") (pintype "bidirectional"))
      (node (ref "Y1") (pin "1") (pinfunction "1_1") (pintype "passive"))
    )
    (net (code "49") (name "Net-(IC3-PB7(XTAL2{slash}TOSC2))") (class "Default")
      (node (ref "IC3") (pin "8") (pinfunction "PB7(XTAL2/TOSC2)_8") (pintype "bidirectional"))
      (node (ref "Y1") (pin "3") (pinfunction "3_3") (pintype "passive"))
    )
    (net (code "50") (name "Net-(IC4-FB)") (class "Default")
      (node (ref "IC4") (pin "3") (pinfunction "FB_3") (pintype "bidirectional"))
      (node (ref "R20") (pin "2") (pinfunction "2_2") (pintype "passive"))
      (node (ref "R21") (pin "1") (pinfunction "1_1") (pintype "passive"))
    )
    (net (code "51") (name "Net-(IC4-SW)") (class "Default")
      (node (ref "D4") (pin "A") (pinfunction "A_A") (pintype "passive"))
      (node (ref "IC4") (pin "1") (pinfunction "SW_1") (pintype "bidirectional"))
      (node (ref "L1") (pin "1") (pinfunction "1_1") (pintype "passive"))
    )
    (net (code "52") (name "Net-(J1A-S)") (class "Default")
      (node (ref "F1") (pin "1") (pinfunction "1_1") (pintype "passive"))
      (node (ref "F1.1") (pin "1") (pinfunction "1_1") (pintype "passive"))
      (node (ref "J1") (pin "1") (pinfunction "S_1") (pintype "passive"))
      (node (ref "X1") (pin "1") (pinfunction "KL_1") (pintype "passive"))
      (node (ref "X1.1") (pin "1") (pinfunction "KL_1") (pintype "passive"))
    )
    (net (code "53") (name "Net-(J2-D+)") (class "Default")
      (node (ref "J2") (pin "P3") (pinfunction "D+_P3") (pintype "bidirectional"))
      (node (ref "R2") (pin "2") (pinfunction "2_2") (pintype "passive"))
    )
    (net (code "54") (name "Net-(J2-D-)") (class "Default")
      (node (ref "J2") (pin "P2") (pinfunction "D-_P2") (pintype "bidirectional"))
      (node (ref "R4") (pin "2") (pinfunction "2_2") (pintype "passive"))
    )
    (net (code "55") (name "Net-(J2-VBUS)") (class "Default")
      (node (ref "D3") (pin "A") (pinfunction "A_A") (pintype "passive"))
      (node (ref "J2") (pin "P1") (pinfunction "VBUS_P1") (pintype "power_in"))
    )
    (net (code "56") (name "Net-(LED1-PadA)") (class "Default")
      (node (ref "LED1") (pin "A") (pinfunction "A_A") (pintype "passive"))
      (node (ref "LED1.1") (pin "A") (pinfunction "A_A") (pintype "passive"))
      (node (ref "R8") (pin "2") (pinfunction "2_2") (pintype "passive"))
      (node (ref "R8.1") (pin "2") (pinfunction "2_2") (pintype "passive"))
    )
    (net (code "57") (name "Net-(LED1.3-PadA)") (class "Default")
      (node (ref "LED1.3") (pin "A") (pinfunction "A_A") (pintype "passive"))
      (node (ref "R13") (pin "2") (pinfunction "2_2") (pintype "passive"))
    )
    (net (code "58") (name "Net-(LED2-PadA)") (class "Default")
      (node (ref "LED2") (pin "A") (pinfunction "A_A") (pintype "passive"))
      (node (ref "LED2.1") (pin "A") (pinfunction "A_A") (pintype "passive"))
      (node (ref "R9") (pin "2") (pinfunction "2_2") (pintype "passive"))
      (node (ref "R9.1") (pin "2") (pinfunction "2_2") (pintype "passive"))
    )
    (net (code "59") (name "Net-(LED3-PadA)") (class "Default")
      (node (ref "LED3") (pin "A") (pinfunction "A_A") (pintype "passive"))
      (node (ref "LED3.1") (pin "A") (pinfunction "A_A") (pintype "passive"))
      (node (ref "R10") (pin "2") (pinfunction "2_2") (pintype "passive"))
      (node (ref "R10.1") (pin "2") (pinfunction "2_2") (pintype "passive"))
    )
    (net (code "60") (name "Net-(LED4-PadA)") (class "Default")
      (node (ref "LED4") (pin "A") (pinfunction "A_A") (pintype "passive"))
      (node (ref "LED4.1") (pin "A") (pinfunction "A_A") (pintype "passive"))
      (node (ref "R11") (pin "1") (pinfunction "1_1") (pintype "passive"))
      (node (ref "R11.1") (pin "2") (pinfunction "2_2") (pintype "passive"))
    )
    (net (code "61") (name "Net-(R1-Pad2)") (class "Default")
      (node (ref "R1") (pin "2") (pinfunction "2_2") (pintype "passive"))
      (node (ref "RX") (pin "A") (pinfunction "A_A") (pintype "passive"))
    )
    (net (code "62") (name "Net-(R22-Pad2)") (class "Default")
      (node (ref "R22") (pin "2") (pinfunction "2_2") (pintype "passive"))
      (node (ref "RED") (pin "A") (pinfunction "A_A") (pintype "passive"))
    )
    (net (code "63") (name "Net-(S7-O)") (class "Default")
      (node (ref "D1") (pin "C") (pinfunction "C_C") (pintype "passive"))
      (node (ref "D2") (pin "C") (pinfunction "C_C") (pintype "passive"))
      (node (ref "F1") (pin "2") (pinfunction "2_2") (pintype "passive"))
      (node (ref "F1.1") (pin "2") (pinfunction "2_2") (pintype "passive"))
      (node (ref "S7") (pin "P$2") (pinfunction "O_P$2") (pintype "passive"))
    )
    (net (code "64") (name "Net-(SG1-1)") (class "Default")
      (node (ref "JP1") (pin "1") (pinfunction "1_1") (pintype "passive"))
      (node (ref "SG1") (pin "+") (pinfunction "1_+") (pintype "passive"))
    )
    (net (code "65") (name "Net-(U1-RTS)") (class "Default")
      (node (ref "C5") (pin "2") (pinfunction "2_2") (pintype "passive"))
      (node (ref "U1") (pin "4") (pinfunction "RTS_4") (pintype "output"))
    )
    (net (code "66") (name "Net-(U1-RX)") (class "Default")
      (node (ref "R5") (pin "2") (pinfunction "2_2") (pintype "passive"))
      (node (ref "U1") (pin "9") (pinfunction "RX_9") (pintype "input"))
    )
    (net (code "67") (name "Net-(U1-TNOW)") (class "Default")
      (node (ref "R1") (pin "1") (pinfunction "1_1") (pintype "passive"))
      (node (ref "U1") (pin "6") (pinfunction "TNOW_6") (pintype "output"))
    )
    (net (code "68") (name "Net-(U1-TX)") (class "Default")
      (node (ref "R3") (pin "2") (pinfunction "2_2") (pintype "passive"))
      (node (ref "U1") (pin "8") (pinfunction "TX_8") (pintype "output"))
    )
    (net (code "69") (name "unconnected-(J2-ID-PadP4)") (class "Default")
      (node (ref "J2") (pin "P4") (pinfunction "ID_P4") (pintype "bidirectional"))
    )
    (net (code "70") (name "unconnected-(S7-P$1-PadP$4)") (class "Default")
      (node (ref "S7") (pin "P$4") (pinfunction "P$1_P$4") (pintype "passive"))
    )
    (net (code "71") (name "unconnected-(S7-P$2-PadP$5)") (class "Default")
      (node (ref "S7") (pin "P$5") (pinfunction "P$2_P$5") (pintype "bidirectional"))
    )
    (net (code "72") (name "unconnected-(U1-CTS-Pad5)") (class "Default")
      (node (ref "U1") (pin "5") (pinfunction "CTS_5") (pintype "input"))
    )
  )
)
